# UI_Ticketing_Slave.net
KiCad netlist of a schematic drawn in Altium Designer
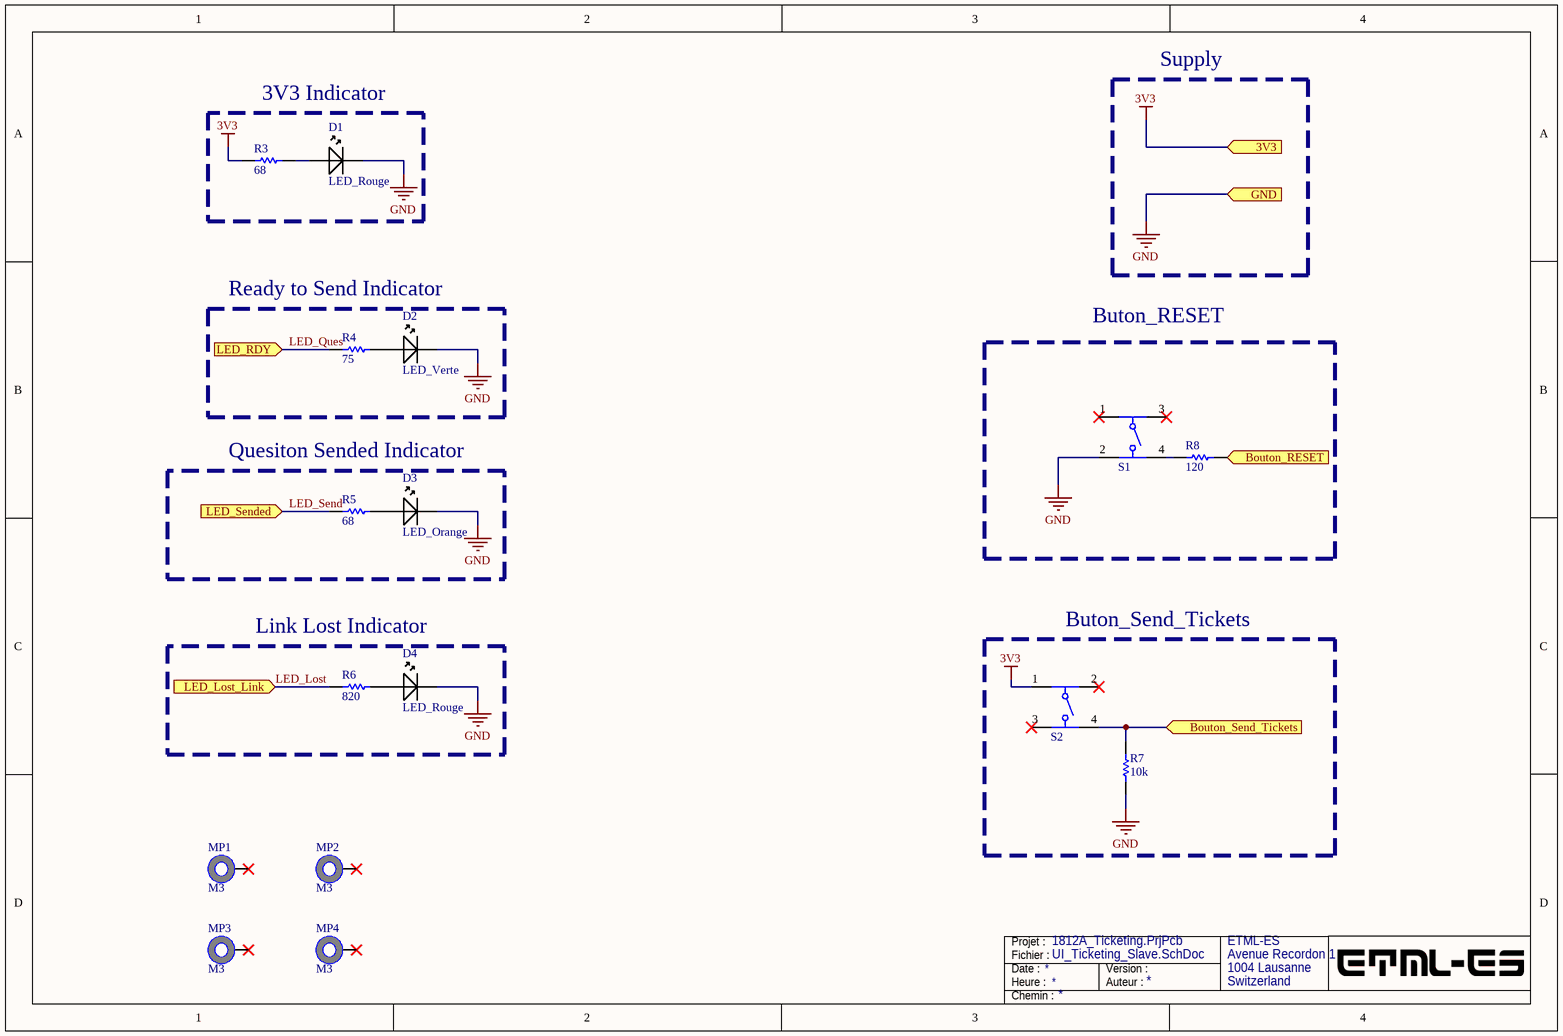
[diagram p0: UI_Ticketing_Slave.SchDoc]

(export (version "E")
  (design (tool "Eeschema 10.0.6"))
  (components
    (comp (ref "D1")
      (value "LED_Rouge")
      (footprint "LED-2P-2.28-3MM")
      (description "LED")
      (libsource (lib "Spectrometre_Lib") (part "LED"))
    )
    (comp (ref "D2")
      (value "LED_Verte")
      (footprint "Type 5mm")
      (description "LED")
      (libsource (lib "") (part "LED_1"))
    )
    (comp (ref "D3")
      (value "LED_Orange")
      (footprint "Type 5mm")
      (description "LED")
      (libsource (lib "") (part "LED_1"))
    )
    (comp (ref "D4")
      (value "LED_Rouge")
      (footprint "Type 5mm")
      (description "LED")
      (libsource (lib "") (part "LED_1"))
    )
    (comp (ref "MP1")
      (value "M3")
      (footprint "9774010151")
      (description "WA-SMSI SMT Steel Spacer, M2.5 Thread Internal, Length 1mm")
      (fields (field (name "PARTNUMBER") "9774010151") (field (name "PUBLISHER") "Wurth Elektronik"))
      (libsource (lib "ALTIUM-SMSI_SMT_STEEL_SPACER_M2_5_THREAD_INTERNAL-rev16b") (part "9774010151"))
    )
    (comp (ref "MP2")
      (value "M3")
      (footprint "9774010151")
      (description "WA-SMSI SMT Steel Spacer, M2.5 Thread Internal, Length 1mm")
      (fields (field (name "PARTNUMBER") "9774010151") (field (name "PUBLISHER") "Wurth Elektronik"))
      (libsource (lib "ALTIUM-SMSI_SMT_STEEL_SPACER_M2_5_THREAD_INTERNAL-rev16b") (part "9774010151"))
    )
    (comp (ref "MP3")
      (value "M3")
      (footprint "9774010151")
      (description "WA-SMSI SMT Steel Spacer, M2.5 Thread Internal, Length 1mm")
      (fields (field (name "PARTNUMBER") "9774010151") (field (name "PUBLISHER") "Wurth Elektronik"))
      (libsource (lib "ALTIUM-SMSI_SMT_STEEL_SPACER_M2_5_THREAD_INTERNAL-rev16b") (part "9774010151"))
    )
    (comp (ref "MP4")
      (value "M3")
      (footprint "9774010151")
      (description "WA-SMSI SMT Steel Spacer, M2.5 Thread Internal, Length 1mm")
      (fields (field (name "PARTNUMBER") "9774010151") (field (name "PUBLISHER") "Wurth Elektronik"))
      (libsource (lib "ALTIUM-SMSI_SMT_STEEL_SPACER_M2_5_THREAD_INTERNAL-rev16b") (part "9774010151"))
    )
    (comp (ref "R3")
      (value "68")
      (footprint "RESC0805(2012)_L")
      (description "100K 0.125W 5% 0805 (2012 Metric)  SMD")
      (fields (field (name "TOLERANCE") "5 %") (field (name "POWER") "0.125 W"))
      (libsource (lib "Altium Content Vault") (part "CMP-1013-00122-1"))
    )
    (comp (ref "R4")
      (value "75")
      (footprint "RESC0805(2012)_L")
      (description "100K 0.125W 5% 0805 (2012 Metric)  SMD")
      (fields (field (name "TOLERANCE") "5 %") (field (name "POWER") "0.125 W"))
      (libsource (lib "Altium Content Vault") (part "CMP-1013-00122-1"))
    )
    (comp (ref "R5")
      (value "68")
      (footprint "RESC0805(2012)_L")
      (description "100K 0.125W 5% 0805 (2012 Metric)  SMD")
      (fields (field (name "TOLERANCE") "5 %") (field (name "POWER") "0.125 W"))
      (libsource (lib "Altium Content Vault") (part "CMP-1013-00122-1"))
    )
    (comp (ref "R6")
      (value "820")
      (footprint "RESC0805(2012)_L")
      (description "100K 0.125W 5% 0805 (2012 Metric)  SMD")
      (fields (field (name "TOLERANCE") "5 %") (field (name "POWER") "0.125 W"))
      (libsource (lib "Altium Content Vault") (part "CMP-1013-00122-1"))
    )
    (comp (ref "R7")
      (value "10k")
      (footprint "RESC0805(2012)_L")
      (description "100K 0.125W 5% 0805 (2012 Metric)  SMD")
      (fields (field (name "TOLERANCE") "5 %") (field (name "POWER") "0.125 W"))
      (libsource (lib "Altium Content Vault") (part "CMP-1013-00122-1"))
    )
    (comp (ref "R8")
      (value "120")
      (footprint "RESC0805(2012)_L")
      (description "100K 0.125W 5% 0805 (2012 Metric)  SMD")
      (fields (field (name "TOLERANCE") "5 %") (field (name "POWER") "0.125 W"))
      (libsource (lib "Altium Content Vault") (part "CMP-1013-00122-1"))
    )
    (comp (ref "S1")
      (value "430182050816")
      (footprint "430182050816")
      (description "6x6mm SMD Tact Switch WS-TASV, height 5 mm, 160 gf")
      (fields (field (name "PUBLISHER") "Wurth Elektronik"))
      (libsource (lib "ALTIUM-WS-TASV-rev17b") (part "430182050816"))
    )
    (comp (ref "S2")
      (value "430466073726")
      (footprint "4304x60737x6_12x12x7.3")
      (description "WS-TATV 12x12mm washable Tact Switch, THT version")
      (fields (field (name "PUBLISHER") "Wurth Elektronik"))
      (libsource (lib "ALTIUM-WS-TATV-rev17a") (part "430466073726"))
    )
  )
  (nets
    (net (code "1") (name "/Bouton_RESET") (class "Default")
      (node (ref "R8") (pin "2") (pinfunction "2_2") (pintype "passive"))
    )
    (net (code "2") (name "/Bouton_Send_Tickets") (class "Default")
      (node (ref "R7") (pin "1") (pinfunction "1_1") (pintype "passive"))
      (node (ref "S2") (pin "4") (pinfunction "4_4") (pintype "passive"))
    )
    (net (code "3") (name "/LED_Lost") (class "Default")
      (node (ref "R6") (pin "2") (pinfunction "2_2") (pintype "passive"))
    )
    (net (code "4") (name "/LED_Ques") (class "Default")
      (node (ref "R4") (pin "2") (pinfunction "2_2") (pintype "passive"))
    )
    (net (code "5") (name "/LED_Send") (class "Default")
      (node (ref "R5") (pin "2") (pinfunction "2_2") (pintype "passive"))
    )
    (net (code "6") (name "3V3") (class "Default")
      (node (ref "R3") (pin "2") (pinfunction "2_2") (pintype "passive"))
      (node (ref "S2") (pin "1") (pinfunction "1_1") (pintype "passive"))
    )
    (net (code "7") (name "GND") (class "Default")
      (node (ref "D1") (pin "2") (pinfunction "Cathode_2") (pintype "passive"))
      (node (ref "D2") (pin "1") (pinfunction "Cathode_1") (pintype "passive"))
      (node (ref "D3") (pin "1") (pinfunction "Cathode_1") (pintype "passive"))
      (node (ref "D4") (pin "1") (pinfunction "Cathode_1") (pintype "passive"))
      (node (ref "R7") (pin "2") (pinfunction "2_2") (pintype "passive"))
      (node (ref "S1") (pin "2") (pinfunction "2_2") (pintype "passive"))
    )
    (net (code "8") (name "Net-(D1-Anode)") (class "Default")
      (node (ref "D1") (pin "1") (pinfunction "Anode_1") (pintype "passive"))
      (node (ref "R3") (pin "1") (pinfunction "1_1") (pintype "passive"))
    )
    (net (code "9") (name "Net-(D2-Anode)") (class "Default")
      (node (ref "D2") (pin "2") (pinfunction "Anode_2") (pintype "passive"))
      (node (ref "R4") (pin "1") (pinfunction "1_1") (pintype "passive"))
    )
    (net (code "10") (name "Net-(D3-Anode)") (class "Default")
      (node (ref "D3") (pin "2") (pinfunction "Anode_2") (pintype "passive"))
      (node (ref "R5") (pin "1") (pinfunction "1_1") (pintype "passive"))
    )
    (net (code "11") (name "Net-(D4-Anode)") (class "Default")
      (node (ref "D4") (pin "2") (pinfunction "Anode_2") (pintype "passive"))
      (node (ref "R6") (pin "1") (pinfunction "1_1") (pintype "passive"))
    )
    (net (code "12") (name "Net-(R8-Pad1)") (class "Default")
      (node (ref "R8") (pin "1") (pinfunction "1_1") (pintype "passive"))
      (node (ref "S1") (pin "4") (pinfunction "4_4") (pintype "passive"))
    )
    (net (code "13") (name "unconnected-(MP1-Pad1)") (class "Default")
      (node (ref "MP1") (pin "1") (pinfunction "1_1") (pintype "passive+no_connect"))
    )
    (net (code "14") (name "unconnected-(MP2-Pad1)") (class "Default")
      (node (ref "MP2") (pin "1") (pinfunction "1_1") (pintype "passive+no_connect"))
    )
    (net (code "15") (name "unconnected-(MP3-Pad1)") (class "Default")
      (node (ref "MP3") (pin "1") (pinfunction "1_1") (pintype "passive+no_connect"))
    )
    (net (code "16") (name "unconnected-(MP4-Pad1)") (class "Default")
      (node (ref "MP4") (pin "1") (pinfunction "1_1") (pintype "passive+no_connect"))
    )
    (net (code "17") (name "unconnected-(S1-Pad1)") (class "Default")
      (node (ref "S1") (pin "1") (pinfunction "1_1") (pintype "passive+no_connect"))
    )
    (net (code "18") (name "unconnected-(S1-Pad3)") (class "Default")
      (node (ref "S1") (pin "3") (pinfunction "3_3") (pintype "passive+no_connect"))
    )
    (net (code "19") (name "unconnected-(S2-Pad2)") (class "Default")
      (node (ref "S2") (pin "2") (pinfunction "2_2") (pintype "passive+no_connect"))
    )
    (net (code "20") (name "unconnected-(S2-Pad3)") (class "Default")
      (node (ref "S2") (pin "3") (pinfunction "3_3") (pintype "passive+no_connect"))
    )
  )
)
